# DTLJ_hexIO_v2.net
KiCad netlist of a schematic drawn in EAGLE
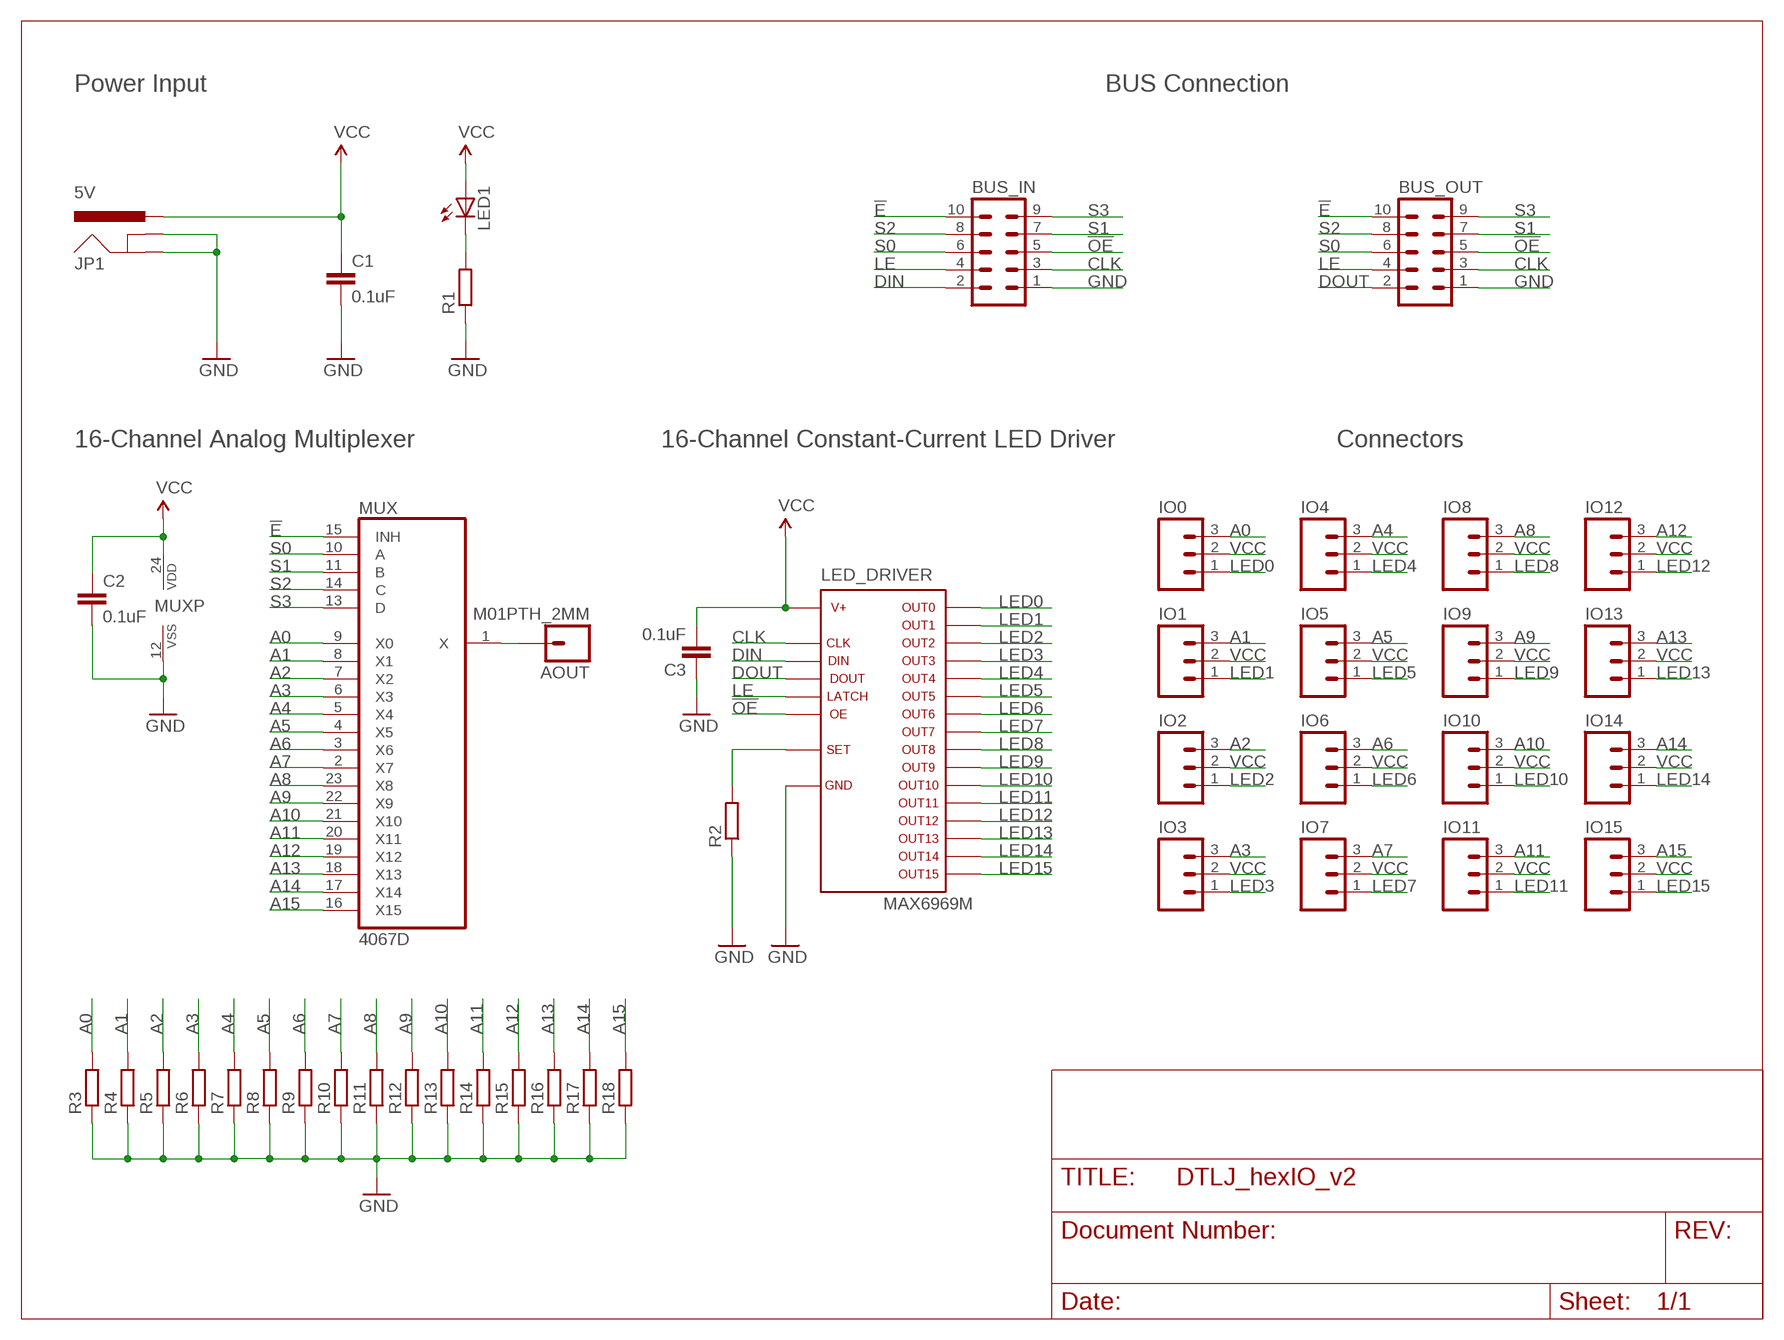
[diagram p0: schematic, sheet 1]

(export (version "E")
  (design (tool "Eeschema 10.0.6"))
  (components
    (comp (ref "AOUT")
      (value "M01PTH_2MM")
      (footprint "eagle-import:1X01_2MM")
      (libsource (lib "eagle-import") (part "M01PTH_2MM"))
    )
    (comp (ref "BUS_IN")
      (value "ML10")
      (footprint "eagle-import:ML10")
      (libsource (lib "eagle-import") (part "ML10"))
    )
    (comp (ref "BUS_OUT")
      (value "ML10")
      (footprint "eagle-import:ML10")
      (libsource (lib "eagle-import") (part "ML10"))
    )
    (comp (ref "C1")
      (value "0.1uF")
      (footprint "eagle-import:C1206")
      (libsource (lib "eagle-import") (part "C-EUC1206"))
    )
    (comp (ref "C2")
      (value "0.1uF")
      (footprint "eagle-import:C1206")
      (libsource (lib "eagle-import") (part "C-EUC1206"))
    )
    (comp (ref "C3")
      (value "0.1uF")
      (footprint "eagle-import:C1206")
      (libsource (lib "eagle-import") (part "C-EUC1206"))
    )
    (comp (ref "IO0")
      (value "M03POLAR")
      (footprint "eagle-import:MOLEX-1X3")
      (libsource (lib "eagle-import") (part "M03POLAR"))
    )
    (comp (ref "IO1")
      (value "M03POLAR")
      (footprint "eagle-import:MOLEX-1X3")
      (libsource (lib "eagle-import") (part "M03POLAR"))
    )
    (comp (ref "IO2")
      (value "M03POLAR")
      (footprint "eagle-import:MOLEX-1X3")
      (libsource (lib "eagle-import") (part "M03POLAR"))
    )
    (comp (ref "IO3")
      (value "M03POLAR")
      (footprint "eagle-import:MOLEX-1X3")
      (libsource (lib "eagle-import") (part "M03POLAR"))
    )
    (comp (ref "IO4")
      (value "M03POLAR")
      (footprint "eagle-import:MOLEX-1X3")
      (libsource (lib "eagle-import") (part "M03POLAR"))
    )
    (comp (ref "IO5")
      (value "M03POLAR")
      (footprint "eagle-import:MOLEX-1X3")
      (libsource (lib "eagle-import") (part "M03POLAR"))
    )
    (comp (ref "IO6")
      (value "M03POLAR")
      (footprint "eagle-import:MOLEX-1X3")
      (libsource (lib "eagle-import") (part "M03POLAR"))
    )
    (comp (ref "IO7")
      (value "M03POLAR")
      (footprint "eagle-import:MOLEX-1X3")
      (libsource (lib "eagle-import") (part "M03POLAR"))
    )
    (comp (ref "IO8")
      (value "M03POLAR")
      (footprint "eagle-import:MOLEX-1X3")
      (libsource (lib "eagle-import") (part "M03POLAR"))
    )
    (comp (ref "IO9")
      (value "M03POLAR")
      (footprint "eagle-import:MOLEX-1X3")
      (libsource (lib "eagle-import") (part "M03POLAR"))
    )
    (comp (ref "IO10")
      (value "M03POLAR")
      (footprint "eagle-import:MOLEX-1X3")
      (libsource (lib "eagle-import") (part "M03POLAR"))
    )
    (comp (ref "IO11")
      (value "M03POLAR")
      (footprint "eagle-import:MOLEX-1X3")
      (libsource (lib "eagle-import") (part "M03POLAR"))
    )
    (comp (ref "IO12")
      (value "M03POLAR")
      (footprint "eagle-import:MOLEX-1X3")
      (libsource (lib "eagle-import") (part "M03POLAR"))
    )
    (comp (ref "IO13")
      (value "M03POLAR")
      (footprint "eagle-import:MOLEX-1X3")
      (libsource (lib "eagle-import") (part "M03POLAR"))
    )
    (comp (ref "IO14")
      (value "M03POLAR")
      (footprint "eagle-import:MOLEX-1X3")
      (libsource (lib "eagle-import") (part "M03POLAR"))
    )
    (comp (ref "IO15")
      (value "M03POLAR")
      (footprint "eagle-import:MOLEX-1X3")
      (libsource (lib "eagle-import") (part "M03POLAR"))
    )
    (comp (ref "JP1")
      (value "5V")
      (footprint "eagle-import:POWER_JACK_PTH_BREAD")
      (libsource (lib "eagle-import") (part "POWER_JACKPTH_BREAD"))
    )
    (comp (ref "LED1")
      (value "LEDSMT1206")
      (footprint "eagle-import:1206")
      (libsource (lib "eagle-import") (part "LEDSMT1206"))
    )
    (comp (ref "LED_DRIVER")
      (value "MAX6969M")
      (footprint "eagle-import:SO24W")
      (libsource (lib "eagle-import") (part "MAX6969M"))
    )
    (comp (ref "MUX")
      (value "4067D")
      (footprint "eagle-import:SO24W")
      (libsource (lib "eagle-import") (part "4067D"))
    )
    (comp (ref "R1")
      (value "R-EU_R1206")
      (footprint "eagle-import:R1206")
      (libsource (lib "eagle-import") (part "R-EU_R1206"))
    )
    (comp (ref "R2")
      (value "R-EU_R1206")
      (footprint "eagle-import:R1206")
      (libsource (lib "eagle-import") (part "R-EU_R1206"))
    )
    (comp (ref "R3")
      (value "R-EU_R1206")
      (footprint "eagle-import:R1206")
      (libsource (lib "eagle-import") (part "R-EU_R1206"))
    )
    (comp (ref "R4")
      (value "R-EU_R1206")
      (footprint "eagle-import:R1206")
      (libsource (lib "eagle-import") (part "R-EU_R1206"))
    )
    (comp (ref "R5")
      (value "R-EU_R1206")
      (footprint "eagle-import:R1206")
      (libsource (lib "eagle-import") (part "R-EU_R1206"))
    )
    (comp (ref "R6")
      (value "R-EU_R1206")
      (footprint "eagle-import:R1206")
      (libsource (lib "eagle-import") (part "R-EU_R1206"))
    )
    (comp (ref "R7")
      (value "R-EU_R1206")
      (footprint "eagle-import:R1206")
      (libsource (lib "eagle-import") (part "R-EU_R1206"))
    )
    (comp (ref "R8")
      (value "R-EU_R1206")
      (footprint "eagle-import:R1206")
      (libsource (lib "eagle-import") (part "R-EU_R1206"))
    )
    (comp (ref "R9")
      (value "R-EU_R1206")
      (footprint "eagle-import:R1206")
      (libsource (lib "eagle-import") (part "R-EU_R1206"))
    )
    (comp (ref "R10")
      (value "R-EU_R1206")
      (footprint "eagle-import:R1206")
      (libsource (lib "eagle-import") (part "R-EU_R1206"))
    )
    (comp (ref "R11")
      (value "R-EU_R1206")
      (footprint "eagle-import:R1206")
      (libsource (lib "eagle-import") (part "R-EU_R1206"))
    )
    (comp (ref "R12")
      (value "R-EU_R1206")
      (footprint "eagle-import:R1206")
      (libsource (lib "eagle-import") (part "R-EU_R1206"))
    )
    (comp (ref "R13")
      (value "R-EU_R1206")
      (footprint "eagle-import:R1206")
      (libsource (lib "eagle-import") (part "R-EU_R1206"))
    )
    (comp (ref "R14")
      (value "R-EU_R1206")
      (footprint "eagle-import:R1206")
      (libsource (lib "eagle-import") (part "R-EU_R1206"))
    )
    (comp (ref "R15")
      (value "R-EU_R1206")
      (footprint "eagle-import:R1206")
      (libsource (lib "eagle-import") (part "R-EU_R1206"))
    )
    (comp (ref "R16")
      (value "R-EU_R1206")
      (footprint "eagle-import:R1206")
      (libsource (lib "eagle-import") (part "R-EU_R1206"))
    )
    (comp (ref "R17")
      (value "R-EU_R1206")
      (footprint "eagle-import:R1206")
      (libsource (lib "eagle-import") (part "R-EU_R1206"))
    )
    (comp (ref "R18")
      (value "R-EU_R1206")
      (footprint "eagle-import:R1206")
      (libsource (lib "eagle-import") (part "R-EU_R1206"))
    )
  )
  (nets
    (net (code "1") (name "/A0") (class "Default")
      (node (ref "IO0") (pin "3") (pinfunction "3_3") (pintype "passive"))
      (node (ref "MUX") (pin "9") (pinfunction "X0_9") (pintype "input"))
      (node (ref "R3") (pin "2") (pinfunction "2_2") (pintype "passive"))
    )
    (net (code "2") (name "/A1") (class "Default")
      (node (ref "IO1") (pin "3") (pinfunction "3_3") (pintype "passive"))
      (node (ref "MUX") (pin "8") (pinfunction "X1_8") (pintype "input"))
      (node (ref "R4") (pin "2") (pinfunction "2_2") (pintype "passive"))
    )
    (net (code "3") (name "/A2") (class "Default")
      (node (ref "IO2") (pin "3") (pinfunction "3_3") (pintype "passive"))
      (node (ref "MUX") (pin "7") (pinfunction "X2_7") (pintype "input"))
      (node (ref "R5") (pin "2") (pinfunction "2_2") (pintype "passive"))
    )
    (net (code "4") (name "/A3") (class "Default")
      (node (ref "IO3") (pin "3") (pinfunction "3_3") (pintype "passive"))
      (node (ref "MUX") (pin "6") (pinfunction "X3_6") (pintype "input"))
      (node (ref "R6") (pin "2") (pinfunction "2_2") (pintype "passive"))
    )
    (net (code "5") (name "/A4") (class "Default")
      (node (ref "IO4") (pin "3") (pinfunction "3_3") (pintype "passive"))
      (node (ref "MUX") (pin "5") (pinfunction "X4_5") (pintype "input"))
      (node (ref "R7") (pin "2") (pinfunction "2_2") (pintype "passive"))
    )
    (net (code "6") (name "/A5") (class "Default")
      (node (ref "IO5") (pin "3") (pinfunction "3_3") (pintype "passive"))
      (node (ref "MUX") (pin "4") (pinfunction "X5_4") (pintype "input"))
      (node (ref "R8") (pin "2") (pinfunction "2_2") (pintype "passive"))
    )
    (net (code "7") (name "/A6") (class "Default")
      (node (ref "IO6") (pin "3") (pinfunction "3_3") (pintype "passive"))
      (node (ref "MUX") (pin "3") (pinfunction "X6_3") (pintype "input"))
      (node (ref "R9") (pin "2") (pinfunction "2_2") (pintype "passive"))
    )
    (net (code "8") (name "/A7") (class "Default")
      (node (ref "IO7") (pin "3") (pinfunction "3_3") (pintype "passive"))
      (node (ref "MUX") (pin "2") (pinfunction "X7_2") (pintype "input"))
      (node (ref "R10") (pin "2") (pinfunction "2_2") (pintype "passive"))
    )
    (net (code "9") (name "/A8") (class "Default")
      (node (ref "IO8") (pin "3") (pinfunction "3_3") (pintype "passive"))
      (node (ref "MUX") (pin "23") (pinfunction "X8_23") (pintype "input"))
      (node (ref "R11") (pin "2") (pinfunction "2_2") (pintype "passive"))
    )
    (net (code "10") (name "/A9") (class "Default")
      (node (ref "IO9") (pin "3") (pinfunction "3_3") (pintype "passive"))
      (node (ref "MUX") (pin "22") (pinfunction "X9_22") (pintype "input"))
      (node (ref "R12") (pin "2") (pinfunction "2_2") (pintype "passive"))
    )
    (net (code "11") (name "/A10") (class "Default")
      (node (ref "IO10") (pin "3") (pinfunction "3_3") (pintype "passive"))
      (node (ref "MUX") (pin "21") (pinfunction "X10_21") (pintype "input"))
      (node (ref "R13") (pin "2") (pinfunction "2_2") (pintype "passive"))
    )
    (net (code "12") (name "/A11") (class "Default")
      (node (ref "IO11") (pin "3") (pinfunction "3_3") (pintype "passive"))
      (node (ref "MUX") (pin "20") (pinfunction "X11_20") (pintype "input"))
      (node (ref "R14") (pin "2") (pinfunction "2_2") (pintype "passive"))
    )
    (net (code "13") (name "/A12") (class "Default")
      (node (ref "IO12") (pin "3") (pinfunction "3_3") (pintype "passive"))
      (node (ref "MUX") (pin "19") (pinfunction "X12_19") (pintype "input"))
      (node (ref "R15") (pin "2") (pinfunction "2_2") (pintype "passive"))
    )
    (net (code "14") (name "/A13") (class "Default")
      (node (ref "IO13") (pin "3") (pinfunction "3_3") (pintype "passive"))
      (node (ref "MUX") (pin "18") (pinfunction "X13_18") (pintype "input"))
      (node (ref "R16") (pin "2") (pinfunction "2_2") (pintype "passive"))
    )
    (net (code "15") (name "/A14") (class "Default")
      (node (ref "IO14") (pin "3") (pinfunction "3_3") (pintype "passive"))
      (node (ref "MUX") (pin "17") (pinfunction "X14_17") (pintype "input"))
      (node (ref "R17") (pin "2") (pinfunction "2_2") (pintype "passive"))
    )
    (net (code "16") (name "/A15") (class "Default")
      (node (ref "IO15") (pin "3") (pinfunction "3_3") (pintype "passive"))
      (node (ref "MUX") (pin "16") (pinfunction "X15_16") (pintype "input"))
      (node (ref "R18") (pin "2") (pinfunction "2_2") (pintype "passive"))
    )
    (net (code "17") (name "/CLK") (class "Default")
      (node (ref "BUS_IN") (pin "3") (pinfunction "3_3") (pintype "passive"))
      (node (ref "BUS_OUT") (pin "3") (pinfunction "3_3") (pintype "passive"))
      (node (ref "LED_DRIVER") (pin "3") (pinfunction "P$3_3") (pintype "input"))
    )
    (net (code "18") (name "/DIN") (class "Default")
      (node (ref "BUS_IN") (pin "2") (pinfunction "2_2") (pintype "passive"))
      (node (ref "LED_DRIVER") (pin "2") (pinfunction "P$2_2") (pintype "input"))
    )
    (net (code "19") (name "/DOUT") (class "Default")
      (node (ref "BUS_OUT") (pin "2") (pinfunction "2_2") (pintype "passive"))
      (node (ref "LED_DRIVER") (pin "22") (pinfunction "P$22_22") (pintype "output"))
    )
    (net (code "20") (name "/LE") (class "Default")
      (node (ref "BUS_IN") (pin "4") (pinfunction "4_4") (pintype "passive"))
      (node (ref "BUS_OUT") (pin "4") (pinfunction "4_4") (pintype "passive"))
      (node (ref "LED_DRIVER") (pin "4") (pinfunction "P$4_4") (pintype "input"))
    )
    (net (code "21") (name "/LED0") (class "Default")
      (node (ref "IO0") (pin "1") (pinfunction "1_1") (pintype "passive"))
      (node (ref "LED_DRIVER") (pin "5") (pinfunction "P$5_5") (pintype "output"))
    )
    (net (code "22") (name "/LED1") (class "Default")
      (node (ref "IO1") (pin "1") (pinfunction "1_1") (pintype "passive"))
      (node (ref "LED_DRIVER") (pin "6") (pinfunction "P$6_6") (pintype "output"))
    )
    (net (code "23") (name "/LED2") (class "Default")
      (node (ref "IO2") (pin "1") (pinfunction "1_1") (pintype "passive"))
      (node (ref "LED_DRIVER") (pin "7") (pinfunction "P$7_7") (pintype "output"))
    )
    (net (code "24") (name "/LED3") (class "Default")
      (node (ref "IO3") (pin "1") (pinfunction "1_1") (pintype "passive"))
      (node (ref "LED_DRIVER") (pin "8") (pinfunction "P$8_8") (pintype "output"))
    )
    (net (code "25") (name "/LED4") (class "Default")
      (node (ref "IO4") (pin "1") (pinfunction "1_1") (pintype "passive"))
      (node (ref "LED_DRIVER") (pin "9") (pinfunction "P$9_9") (pintype "output"))
    )
    (net (code "26") (name "/LED5") (class "Default")
      (node (ref "IO5") (pin "1") (pinfunction "1_1") (pintype "passive"))
      (node (ref "LED_DRIVER") (pin "10") (pinfunction "P$10_10") (pintype "output"))
    )
    (net (code "27") (name "/LED6") (class "Default")
      (node (ref "IO6") (pin "1") (pinfunction "1_1") (pintype "passive"))
      (node (ref "LED_DRIVER") (pin "11") (pinfunction "P$11_11") (pintype "output"))
    )
    (net (code "28") (name "/LED7") (class "Default")
      (node (ref "IO7") (pin "1") (pinfunction "1_1") (pintype "passive"))
      (node (ref "LED_DRIVER") (pin "12") (pinfunction "P$12_12") (pintype "output"))
    )
    (net (code "29") (name "/LED8") (class "Default")
      (node (ref "IO8") (pin "1") (pinfunction "1_1") (pintype "passive"))
      (node (ref "LED_DRIVER") (pin "13") (pinfunction "P$13_13") (pintype "output"))
    )
    (net (code "30") (name "/LED9") (class "Default")
      (node (ref "IO9") (pin "1") (pinfunction "1_1") (pintype "passive"))
      (node (ref "LED_DRIVER") (pin "14") (pinfunction "P$14_14") (pintype "output"))
    )
    (net (code "31") (name "/LED10") (class "Default")
      (node (ref "IO10") (pin "1") (pinfunction "1_1") (pintype "passive"))
      (node (ref "LED_DRIVER") (pin "15") (pinfunction "P$15_15") (pintype "output"))
    )
    (net (code "32") (name "/LED11") (class "Default")
      (node (ref "IO11") (pin "1") (pinfunction "1_1") (pintype "passive"))
      (node (ref "LED_DRIVER") (pin "16") (pinfunction "P$16_16") (pintype "output"))
    )
    (net (code "33") (name "/LED12") (class "Default")
      (node (ref "IO12") (pin "1") (pinfunction "1_1") (pintype "passive"))
      (node (ref "LED_DRIVER") (pin "17") (pinfunction "P$17_17") (pintype "output"))
    )
    (net (code "34") (name "/LED13") (class "Default")
      (node (ref "IO13") (pin "1") (pinfunction "1_1") (pintype "passive"))
      (node (ref "LED_DRIVER") (pin "18") (pinfunction "P$18_18") (pintype "output"))
    )
    (net (code "35") (name "/LED14") (class "Default")
      (node (ref "IO14") (pin "1") (pinfunction "1_1") (pintype "passive"))
      (node (ref "LED_DRIVER") (pin "19") (pinfunction "P$19_19") (pintype "output"))
    )
    (net (code "36") (name "/LED15") (class "Default")
      (node (ref "IO15") (pin "1") (pinfunction "1_1") (pintype "passive"))
      (node (ref "LED_DRIVER") (pin "20") (pinfunction "P$20_20") (pintype "output"))
    )
    (net (code "37") (name "/S0") (class "Default")
      (node (ref "BUS_IN") (pin "6") (pinfunction "6_6") (pintype "passive"))
      (node (ref "BUS_OUT") (pin "6") (pinfunction "6_6") (pintype "passive"))
      (node (ref "MUX") (pin "10") (pinfunction "A_10") (pintype "input"))
    )
    (net (code "38") (name "/S1") (class "Default")
      (node (ref "BUS_IN") (pin "7") (pinfunction "7_7") (pintype "passive"))
      (node (ref "BUS_OUT") (pin "7") (pinfunction "7_7") (pintype "passive"))
      (node (ref "MUX") (pin "11") (pinfunction "B_11") (pintype "input"))
    )
    (net (code "39") (name "/S2") (class "Default")
      (node (ref "BUS_IN") (pin "8") (pinfunction "8_8") (pintype "passive"))
      (node (ref "BUS_OUT") (pin "8") (pinfunction "8_8") (pintype "passive"))
      (node (ref "MUX") (pin "14") (pinfunction "C_14") (pintype "input"))
    )
    (net (code "40") (name "/S3") (class "Default")
      (node (ref "BUS_IN") (pin "9") (pinfunction "9_9") (pintype "passive"))
      (node (ref "BUS_OUT") (pin "9") (pinfunction "9_9") (pintype "passive"))
      (node (ref "MUX") (pin "13") (pinfunction "D_13") (pintype "input"))
    )
    (net (code "41") (name "/~{E}") (class "Default")
      (node (ref "BUS_IN") (pin "10") (pinfunction "10_10") (pintype "passive"))
      (node (ref "BUS_OUT") (pin "10") (pinfunction "10_10") (pintype "passive"))
      (node (ref "MUX") (pin "15") (pinfunction "INH_15") (pintype "input"))
    )
    (net (code "42") (name "/~{OE}") (class "Default")
      (node (ref "BUS_IN") (pin "5") (pinfunction "5_5") (pintype "passive"))
      (node (ref "BUS_OUT") (pin "5") (pinfunction "5_5") (pintype "passive"))
      (node (ref "LED_DRIVER") (pin "21") (pinfunction "P$21_21") (pintype "input"))
    )
    (net (code "43") (name "GND") (class "Default")
      (node (ref "BUS_IN") (pin "1") (pinfunction "1_1") (pintype "passive"))
      (node (ref "BUS_OUT") (pin "1") (pinfunction "1_1") (pintype "passive"))
      (node (ref "C1") (pin "2") (pinfunction "2_2") (pintype "passive"))
      (node (ref "C2") (pin "2") (pinfunction "2_2") (pintype "passive"))
      (node (ref "C3") (pin "1") (pinfunction "1_1") (pintype "passive"))
      (node (ref "JP1") (pin "GND") (pinfunction "GND_GND") (pintype "bidirectional"))
      (node (ref "JP1") (pin "GNDBREAK") (pinfunction "GNDBREAK_GNDBREAK") (pintype "bidirectional"))
      (node (ref "LED_DRIVER") (pin "1") (pinfunction "P$1_1") (pintype "power_in"))
      (node (ref "MUX") (pin "12") (pinfunction "VSS_12") (pintype "power_in"))
      (node (ref "R1") (pin "1") (pinfunction "1_1") (pintype "passive"))
      (node (ref "R10") (pin "1") (pinfunction "1_1") (pintype "passive"))
      (node (ref "R11") (pin "1") (pinfunction "1_1") (pintype "passive"))
      (node (ref "R12") (pin "1") (pinfunction "1_1") (pintype "passive"))
      (node (ref "R13") (pin "1") (pinfunction "1_1") (pintype "passive"))
      (node (ref "R14") (pin "1") (pinfunction "1_1") (pintype "passive"))
      (node (ref "R15") (pin "1") (pinfunction "1_1") (pintype "passive"))
      (node (ref "R16") (pin "1") (pinfunction "1_1") (pintype "passive"))
      (node (ref "R17") (pin "1") (pinfunction "1_1") (pintype "passive"))
      (node (ref "R18") (pin "1") (pinfunction "1_1") (pintype "passive"))
      (node (ref "R2") (pin "1") (pinfunction "1_1") (pintype "passive"))
      (node (ref "R3") (pin "1") (pinfunction "1_1") (pintype "passive"))
      (node (ref "R4") (pin "1") (pinfunction "1_1") (pintype "passive"))
      (node (ref "R5") (pin "1") (pinfunction "1_1") (pintype "passive"))
      (node (ref "R6") (pin "1") (pinfunction "1_1") (pintype "passive"))
      (node (ref "R7") (pin "1") (pinfunction "1_1") (pintype "passive"))
      (node (ref "R8") (pin "1") (pinfunction "1_1") (pintype "passive"))
      (node (ref "R9") (pin "1") (pinfunction "1_1") (pintype "passive"))
    )
    (net (code "44") (name "Net-(LED1-PadC)") (class "Default")
      (node (ref "LED1") (pin "C") (pinfunction "C_C") (pintype "passive"))
      (node (ref "R1") (pin "2") (pinfunction "2_2") (pintype "passive"))
    )
    (net (code "45") (name "Net-(LED_DRIVER-P$23)") (class "Default")
      (node (ref "LED_DRIVER") (pin "23") (pinfunction "P$23_23") (pintype "bidirectional"))
      (node (ref "R2") (pin "2") (pinfunction "2_2") (pintype "passive"))
    )
    (net (code "46") (name "Net-(MUXA-X)") (class "Default")
      (node (ref "AOUT") (pin "1") (pinfunction "1_1") (pintype "passive"))
      (node (ref "MUX") (pin "1") (pinfunction "X_1") (pintype "output"))
    )
    (net (code "47") (name "VCC") (class "Default")
      (node (ref "C1") (pin "1") (pinfunction "1_1") (pintype "passive"))
      (node (ref "C2") (pin "1") (pinfunction "1_1") (pintype "passive"))
      (node (ref "C3") (pin "2") (pinfunction "2_2") (pintype "passive"))
      (node (ref "IO0") (pin "2") (pinfunction "2_2") (pintype "passive"))
      (node (ref "IO1") (pin "2") (pinfunction "2_2") (pintype "passive"))
      (node (ref "IO10") (pin "2") (pinfunction "2_2") (pintype "passive"))
      (node (ref "IO11") (pin "2") (pinfunction "2_2") (pintype "passive"))
      (node (ref "IO12") (pin "2") (pinfunction "2_2") (pintype "passive"))
      (node (ref "IO13") (pin "2") (pinfunction "2_2") (pintype "passive"))
      (node (ref "IO14") (pin "2") (pinfunction "2_2") (pintype "passive"))
      (node (ref "IO15") (pin "2") (pinfunction "2_2") (pintype "passive"))
      (node (ref "IO2") (pin "2") (pinfunction "2_2") (pintype "passive"))
      (node (ref "IO3") (pin "2") (pinfunction "2_2") (pintype "passive"))
      (node (ref "IO4") (pin "2") (pinfunction "2_2") (pintype "passive"))
      (node (ref "IO5") (pin "2") (pinfunction "2_2") (pintype "passive"))
      (node (ref "IO6") (pin "2") (pinfunction "2_2") (pintype "passive"))
      (node (ref "IO7") (pin "2") (pinfunction "2_2") (pintype "passive"))
      (node (ref "IO8") (pin "2") (pinfunction "2_2") (pintype "passive"))
      (node (ref "IO9") (pin "2") (pinfunction "2_2") (pintype "passive"))
      (node (ref "JP1") (pin "PWR") (pinfunction "PWR_PWR") (pintype "bidirectional"))
      (node (ref "LED1") (pin "A") (pinfunction "A_A") (pintype "passive"))
      (node (ref "LED_DRIVER") (pin "24") (pinfunction "P$24_24") (pintype "power_in"))
      (node (ref "MUX") (pin "24") (pinfunction "VDD_24") (pintype "power_in"))
    )
  )
)
